# LED_Cube_5x5x5.net
KiCad netlist of a schematic drawn in EAGLE
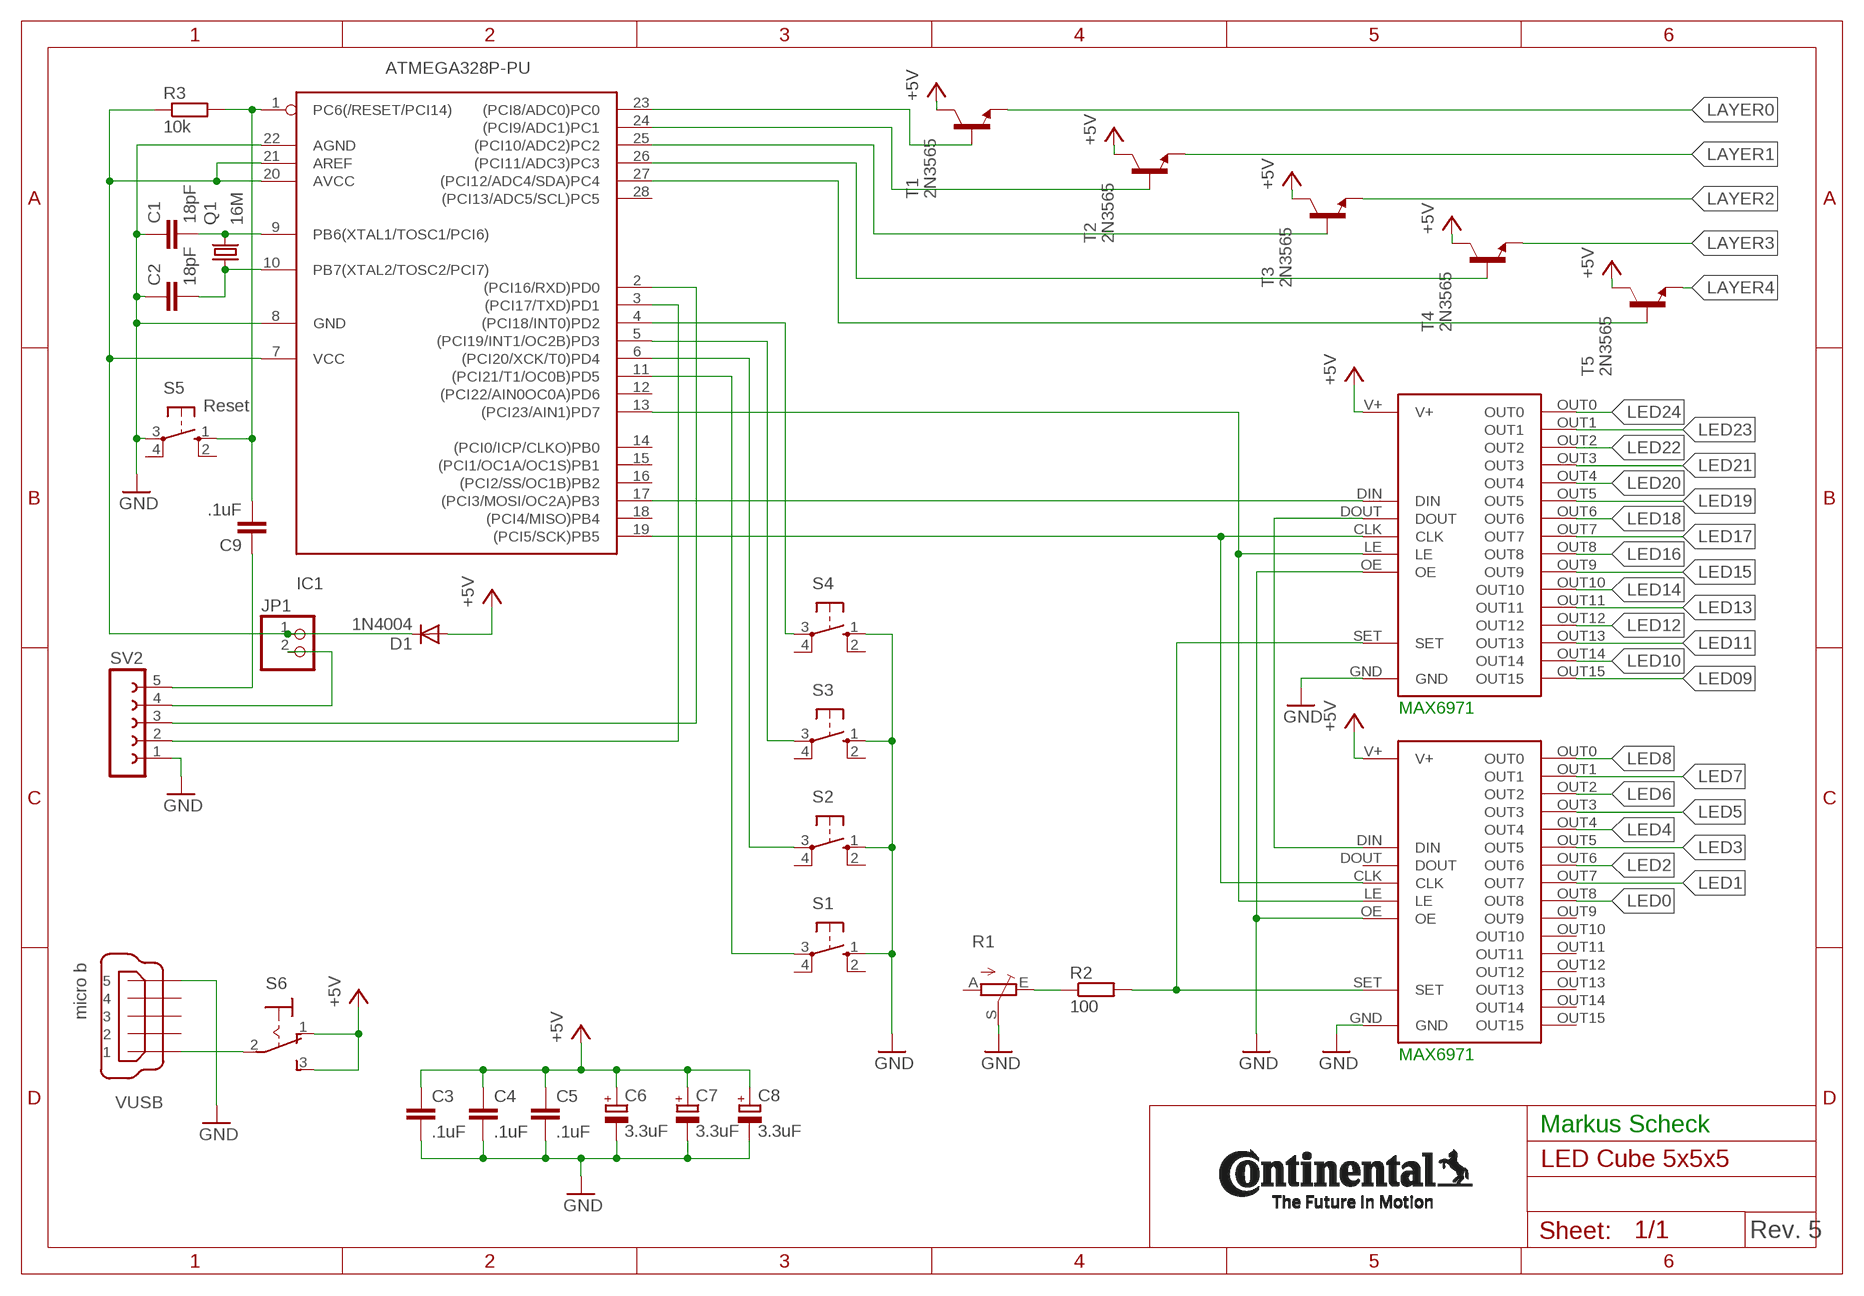
[diagram p0: schematic, sheet 1]

(export (version "E")
  (design (tool "Eeschema 10.0.6"))
  (components
    (comp (ref "C1")
      (value "18pF")
      (footprint "eagle-import:C2.5-3")
      (libsource (lib "eagle-import") (part "C2,5-3"))
    )
    (comp (ref "C2")
      (value "18pF")
      (footprint "eagle-import:C2.5-3")
      (libsource (lib "eagle-import") (part "C2,5-3"))
    )
    (comp (ref "C3")
      (value ".1uF")
      (footprint "eagle-import:C2.5-3")
      (libsource (lib "eagle-import") (part "C2,5-3"))
    )
    (comp (ref "C4")
      (value ".1uF")
      (footprint "eagle-import:C2.5-3")
      (libsource (lib "eagle-import") (part "C2,5-3"))
    )
    (comp (ref "C5")
      (value ".1uF")
      (footprint "eagle-import:C2.5-3")
      (libsource (lib "eagle-import") (part "C2,5-3"))
    )
    (comp (ref "C6")
      (value "3.3uF")
      (footprint "eagle-import:B45181A")
      (libsource (lib "eagle-import") (part "CPOL-EUB45181A"))
    )
    (comp (ref "C7")
      (value "3.3uF")
      (footprint "eagle-import:B45181A")
      (libsource (lib "eagle-import") (part "CPOL-EUB45181A"))
    )
    (comp (ref "C8")
      (value "3.3uF")
      (footprint "eagle-import:B45181A")
      (libsource (lib "eagle-import") (part "CPOL-EUB45181A"))
    )
    (comp (ref "C9")
      (value ".1uF")
      (footprint "eagle-import:C2.5-2")
      (libsource (lib "eagle-import") (part "C2.5/2"))
    )
    (comp (ref "D1")
      (value "1N4004")
      (footprint "eagle-import:DO41-10")
      (libsource (lib "eagle-import") (part "1N4004"))
    )
    (comp (ref "IC1")
      (value "ATMEGA328P-PU")
      (footprint "eagle-import:DIL28-3")
      (libsource (lib "eagle-import") (part "ATMEGA328PV-10"))
    )
    (comp (ref "JP1")
      (value "PINHD-1X2")
      (footprint "eagle-import:1X02")
      (libsource (lib "eagle-import") (part "PINHD-1X2"))
    )
    (comp (ref "Q1")
      (value "16M")
      (footprint "eagle-import:11.4X4.5")
      (libsource (lib "eagle-import") (part "KX-KS"))
    )
    (comp (ref "R1")
      (value "TRIM_EU-CA6V")
      (footprint "eagle-import:CA6V")
      (libsource (lib "eagle-import") (part "TRIM_EU-CA6V"))
    )
    (comp (ref "R2")
      (value "100")
      (footprint "eagle-import:0204_7")
      (libsource (lib "eagle-import") (part "R-EU_0204/7"))
    )
    (comp (ref "R3")
      (value "10k")
      (footprint "eagle-import:0204_7")
      (libsource (lib "eagle-import") (part "R0204/7"))
    )
    (comp (ref "S1")
      (value "10-XX")
      (footprint "eagle-import:B3F-10XX")
      (fields (field (name "MPN") "B3F-1000"))
      (libsource (lib "eagle-import") (part "10-XX"))
    )
    (comp (ref "S2")
      (value "10-XX")
      (footprint "eagle-import:B3F-10XX")
      (fields (field (name "MPN") "B3F-1000"))
      (libsource (lib "eagle-import") (part "10-XX"))
    )
    (comp (ref "S3")
      (value "10-XX")
      (footprint "eagle-import:B3F-10XX")
      (fields (field (name "MPN") "B3F-1000"))
      (libsource (lib "eagle-import") (part "10-XX"))
    )
    (comp (ref "S4")
      (value "10-XX")
      (footprint "eagle-import:B3F-10XX")
      (fields (field (name "MPN") "B3F-1000"))
      (libsource (lib "eagle-import") (part "10-XX"))
    )
    (comp (ref "S5")
      (value "Reset")
      (footprint "eagle-import:B3F-10XX")
      (fields (field (name "MPN") "B3F-1000"))
      (libsource (lib "eagle-import") (part "10-XX"))
    )
    (comp (ref "S6")
      (value "320-916")
      (footprint "eagle-import:320-916")
      (libsource (lib "eagle-import") (part "320-916"))
    )
    (comp (ref "SV2")
      (value "FE05-1")
      (footprint "eagle-import:FE05-1")
      (libsource (lib "eagle-import") (part "FE05-1"))
    )
    (comp (ref "T1")
      (value "2N3565")
      (footprint "eagle-import:TO92")
      (libsource (lib "eagle-import") (part "2N3565"))
    )
    (comp (ref "T2")
      (value "2N3565")
      (footprint "eagle-import:TO92")
      (libsource (lib "eagle-import") (part "2N3565"))
    )
    (comp (ref "T3")
      (value "2N3565")
      (footprint "eagle-import:TO92")
      (libsource (lib "eagle-import") (part "2N3565"))
    )
    (comp (ref "T4")
      (value "2N3565")
      (footprint "eagle-import:TO92")
      (libsource (lib "eagle-import") (part "2N3565"))
    )
    (comp (ref "T5")
      (value "2N3565")
      (footprint "eagle-import:TO92")
      (libsource (lib "eagle-import") (part "2N3565"))
    )
    (comp (ref "U$1")
      (value "MAX6971")
      (footprint "eagle-import:MAX6971")
      (libsource (lib "eagle-import") (part "MAX6971"))
    )
    (comp (ref "U$2")
      (value "MAX6971")
      (footprint "eagle-import:MAX6971")
      (libsource (lib "eagle-import") (part "MAX6971"))
    )
    (comp (ref "VUSB")
      (value "micro b")
      (footprint "eagle-import:32005-201")
      (libsource (lib "eagle-import") (part "MINI-USB-32005-201"))
    )
  )
  (nets
    (net (code "1") (name "+5V") (class "Default")
      (node (ref "C3") (pin "1") (pinfunction "1_1") (pintype "passive"))
      (node (ref "C4") (pin "1") (pinfunction "1_1") (pintype "passive"))
      (node (ref "C5") (pin "1") (pinfunction "1_1") (pintype "passive"))
      (node (ref "C6") (pin "+") (pinfunction "+_+") (pintype "passive"))
      (node (ref "C7") (pin "+") (pinfunction "+_+") (pintype "passive"))
      (node (ref "C8") (pin "+") (pinfunction "+_+") (pintype "passive"))
      (node (ref "D1") (pin "A") (pinfunction "A_A") (pintype "passive"))
      (node (ref "S6") (pin "1") (pinfunction "O_1") (pintype "passive"))
      (node (ref "S6") (pin "3") (pinfunction "S_3") (pintype "passive"))
      (node (ref "T1") (pin "1") (pinfunction "C_1") (pintype "passive"))
      (node (ref "T2") (pin "1") (pinfunction "C_1") (pintype "passive"))
      (node (ref "T3") (pin "1") (pinfunction "C_1") (pintype "passive"))
      (node (ref "T4") (pin "1") (pinfunction "C_1") (pintype "passive"))
      (node (ref "T5") (pin "1") (pinfunction "C_1") (pintype "passive"))
      (node (ref "U$1") (pin "V+") (pinfunction "V+_V+") (pintype "bidirectional"))
      (node (ref "U$2") (pin "V+") (pinfunction "V+_V+") (pintype "bidirectional"))
    )
    (net (code "2") (name "GND") (class "Default")
      (node (ref "C1") (pin "1") (pinfunction "1_1") (pintype "passive"))
      (node (ref "C2") (pin "1") (pinfunction "1_1") (pintype "passive"))
      (node (ref "C3") (pin "2") (pinfunction "2_2") (pintype "passive"))
      (node (ref "C4") (pin "2") (pinfunction "2_2") (pintype "passive"))
      (node (ref "C5") (pin "2") (pinfunction "2_2") (pintype "passive"))
      (node (ref "C6") (pin "-") (pinfunction "-_-") (pintype "passive"))
      (node (ref "C7") (pin "-") (pinfunction "-_-") (pintype "passive"))
      (node (ref "C8") (pin "-") (pinfunction "-_-") (pintype "passive"))
      (node (ref "IC1") (pin "22") (pinfunction "AGND_22") (pintype "bidirectional"))
      (node (ref "IC1") (pin "8") (pinfunction "GND_8") (pintype "bidirectional"))
      (node (ref "R1") (pin "S") (pinfunction "S_S") (pintype "passive"))
      (node (ref "S1") (pin "1") (pinfunction "S_1") (pintype "passive"))
      (node (ref "S2") (pin "1") (pinfunction "S_1") (pintype "passive"))
      (node (ref "S3") (pin "1") (pinfunction "S_1") (pintype "passive"))
      (node (ref "S4") (pin "1") (pinfunction "S_1") (pintype "passive"))
      (node (ref "S5") (pin "3") (pinfunction "P_3") (pintype "passive"))
      (node (ref "SV2") (pin "1") (pinfunction "1_1") (pintype "passive"))
      (node (ref "U$1") (pin "GND") (pinfunction "GND_GND") (pintype "bidirectional"))
      (node (ref "U$1") (pin "OE") (pinfunction "OE_OE") (pintype "bidirectional"))
      (node (ref "U$2") (pin "GND") (pinfunction "GND_GND") (pintype "bidirectional"))
      (node (ref "U$2") (pin "OE") (pinfunction "OE_OE") (pintype "bidirectional"))
      (node (ref "VUSB") (pin "5") (pinfunction "5_5") (pintype "passive"))
    )
    (net (code "3") (name "LAYER0") (class "Default")
      (node (ref "T1") (pin "3") (pinfunction "E_3") (pintype "passive"))
    )
    (net (code "4") (name "LAYER1") (class "Default")
      (node (ref "T2") (pin "3") (pinfunction "E_3") (pintype "passive"))
    )
    (net (code "5") (name "LAYER2") (class "Default")
      (node (ref "T3") (pin "3") (pinfunction "E_3") (pintype "passive"))
    )
    (net (code "6") (name "LAYER3") (class "Default")
      (node (ref "T4") (pin "3") (pinfunction "E_3") (pintype "passive"))
    )
    (net (code "7") (name "LAYER4") (class "Default")
      (node (ref "T5") (pin "3") (pinfunction "E_3") (pintype "passive"))
    )
    (net (code "8") (name "LED0") (class "Default")
      (node (ref "U$1") (pin "OUT8") (pinfunction "OUT8_OUT8") (pintype "bidirectional"))
    )
    (net (code "9") (name "LED1") (class "Default")
      (node (ref "U$1") (pin "OUT7") (pinfunction "OUT7_OUT7") (pintype "bidirectional"))
    )
    (net (code "10") (name "LED2") (class "Default")
      (node (ref "U$1") (pin "OUT6") (pinfunction "OUT6_OUT6") (pintype "bidirectional"))
    )
    (net (code "11") (name "LED3") (class "Default")
      (node (ref "U$1") (pin "OUT5") (pinfunction "OUT5_OUT5") (pintype "bidirectional"))
    )
    (net (code "12") (name "LED4") (class "Default")
      (node (ref "U$1") (pin "OUT4") (pinfunction "OUT4_OUT4") (pintype "bidirectional"))
    )
    (net (code "13") (name "LED5") (class "Default")
      (node (ref "U$1") (pin "OUT3") (pinfunction "OUT3_OUT3") (pintype "bidirectional"))
    )
    (net (code "14") (name "LED6") (class "Default")
      (node (ref "U$1") (pin "OUT2") (pinfunction "OUT2_OUT2") (pintype "bidirectional"))
    )
    (net (code "15") (name "LED7") (class "Default")
      (node (ref "U$1") (pin "OUT1") (pinfunction "OUT1_OUT1") (pintype "bidirectional"))
    )
    (net (code "16") (name "LED8") (class "Default")
      (node (ref "U$1") (pin "OUT0") (pinfunction "OUT0_OUT0") (pintype "bidirectional"))
    )
    (net (code "17") (name "LED09") (class "Default")
      (node (ref "U$2") (pin "OUT15") (pinfunction "OUT15_OUT15") (pintype "bidirectional"))
    )
    (net (code "18") (name "LED10") (class "Default")
      (node (ref "U$2") (pin "OUT14") (pinfunction "OUT14_OUT14") (pintype "bidirectional"))
    )
    (net (code "19") (name "LED11") (class "Default")
      (node (ref "U$2") (pin "OUT13") (pinfunction "OUT13_OUT13") (pintype "bidirectional"))
    )
    (net (code "20") (name "LED12") (class "Default")
      (node (ref "U$2") (pin "OUT12") (pinfunction "OUT12_OUT12") (pintype "bidirectional"))
    )
    (net (code "21") (name "LED13") (class "Default")
      (node (ref "U$2") (pin "OUT11") (pinfunction "OUT11_OUT11") (pintype "bidirectional"))
    )
    (net (code "22") (name "LED14") (class "Default")
      (node (ref "U$2") (pin "OUT10") (pinfunction "OUT10_OUT10") (pintype "bidirectional"))
    )
    (net (code "23") (name "LED15") (class "Default")
      (node (ref "U$2") (pin "OUT9") (pinfunction "OUT9_OUT9") (pintype "bidirectional"))
    )
    (net (code "24") (name "LED16") (class "Default")
      (node (ref "U$2") (pin "OUT8") (pinfunction "OUT8_OUT8") (pintype "bidirectional"))
    )
    (net (code "25") (name "LED17") (class "Default")
      (node (ref "U$2") (pin "OUT7") (pinfunction "OUT7_OUT7") (pintype "bidirectional"))
    )
    (net (code "26") (name "LED18") (class "Default")
      (node (ref "U$2") (pin "OUT6") (pinfunction "OUT6_OUT6") (pintype "bidirectional"))
    )
    (net (code "27") (name "LED19") (class "Default")
      (node (ref "U$2") (pin "OUT5") (pinfunction "OUT5_OUT5") (pintype "bidirectional"))
    )
    (net (code "28") (name "LED20") (class "Default")
      (node (ref "U$2") (pin "OUT4") (pinfunction "OUT4_OUT4") (pintype "bidirectional"))
    )
    (net (code "29") (name "LED21") (class "Default")
      (node (ref "U$2") (pin "OUT3") (pinfunction "OUT3_OUT3") (pintype "bidirectional"))
    )
    (net (code "30") (name "LED22") (class "Default")
      (node (ref "U$2") (pin "OUT2") (pinfunction "OUT2_OUT2") (pintype "bidirectional"))
    )
    (net (code "31") (name "LED23") (class "Default")
      (node (ref "U$2") (pin "OUT1") (pinfunction "OUT1_OUT1") (pintype "bidirectional"))
    )
    (net (code "32") (name "LED24") (class "Default")
      (node (ref "U$2") (pin "OUT0") (pinfunction "OUT0_OUT0") (pintype "bidirectional"))
    )
    (net (code "33") (name "Net-(C9-Pad1)") (class "Default")
      (node (ref "C9") (pin "1") (pinfunction "1_1") (pintype "passive"))
      (node (ref "SV2") (pin "5") (pinfunction "5_5") (pintype "passive"))
    )
    (net (code "34") (name "Net-(IC1-(PCI3{slash}MOSI{slash}OC2A)PB3)") (class "Default")
      (node (ref "IC1") (pin "17") (pinfunction "(PCI3/MOSI/OC2A)PB3_17") (pintype "bidirectional"))
      (node (ref "U$2") (pin "DIN") (pinfunction "DIN_DIN") (pintype "bidirectional"))
    )
    (net (code "35") (name "Net-(IC1-(PCI5{slash}SCK)PB5)") (class "Default")
      (node (ref "IC1") (pin "19") (pinfunction "(PCI5/SCK)PB5_19") (pintype "bidirectional"))
      (node (ref "U$1") (pin "CLK") (pinfunction "CLK_CLK") (pintype "bidirectional"))
      (node (ref "U$2") (pin "CLK") (pinfunction "CLK_CLK") (pintype "bidirectional"))
    )
    (net (code "36") (name "Net-(IC1-(PCI8{slash}ADC0)PC0)") (class "Default")
      (node (ref "IC1") (pin "23") (pinfunction "(PCI8/ADC0)PC0_23") (pintype "bidirectional"))
      (node (ref "T1") (pin "2") (pinfunction "B_2") (pintype "passive"))
    )
    (net (code "37") (name "Net-(IC1-(PCI9{slash}ADC1)PC1)") (class "Default")
      (node (ref "IC1") (pin "24") (pinfunction "(PCI9/ADC1)PC1_24") (pintype "bidirectional"))
      (node (ref "T2") (pin "2") (pinfunction "B_2") (pintype "passive"))
    )
    (net (code "38") (name "Net-(IC1-(PCI10{slash}ADC2)PC2)") (class "Default")
      (node (ref "IC1") (pin "25") (pinfunction "(PCI10/ADC2)PC2_25") (pintype "bidirectional"))
      (node (ref "T3") (pin "2") (pinfunction "B_2") (pintype "passive"))
    )
    (net (code "39") (name "Net-(IC1-(PCI11{slash}ADC3)PC3)") (class "Default")
      (node (ref "IC1") (pin "26") (pinfunction "(PCI11/ADC3)PC3_26") (pintype "bidirectional"))
      (node (ref "T4") (pin "2") (pinfunction "B_2") (pintype "passive"))
    )
    (net (code "40") (name "Net-(IC1-(PCI12{slash}ADC4{slash}SDA)PC4)") (class "Default")
      (node (ref "IC1") (pin "27") (pinfunction "(PCI12/ADC4/SDA)PC4_27") (pintype "bidirectional"))
      (node (ref "T5") (pin "2") (pinfunction "B_2") (pintype "passive"))
    )
    (net (code "41") (name "Net-(IC1-(PCI16{slash}RXD)PD0)") (class "Default")
      (node (ref "IC1") (pin "2") (pinfunction "(PCI16/RXD)PD0_2") (pintype "bidirectional"))
      (node (ref "SV2") (pin "3") (pinfunction "3_3") (pintype "passive"))
    )
    (net (code "42") (name "Net-(IC1-(PCI17{slash}TXD)PD1)") (class "Default")
      (node (ref "IC1") (pin "3") (pinfunction "(PCI17/TXD)PD1_3") (pintype "bidirectional"))
      (node (ref "SV2") (pin "2") (pinfunction "2_2") (pintype "passive"))
    )
    (net (code "43") (name "Net-(IC1-(PCI18{slash}INT0)PD2)") (class "Default")
      (node (ref "IC1") (pin "4") (pinfunction "(PCI18/INT0)PD2_4") (pintype "bidirectional"))
      (node (ref "S4") (pin "3") (pinfunction "P_3") (pintype "passive"))
    )
    (net (code "44") (name "Net-(IC1-(PCI19{slash}INT1{slash}OC2B)PD3)") (class "Default")
      (node (ref "IC1") (pin "5") (pinfunction "(PCI19/INT1/OC2B)PD3_5") (pintype "bidirectional"))
      (node (ref "S3") (pin "3") (pinfunction "P_3") (pintype "passive"))
    )
    (net (code "45") (name "Net-(IC1-(PCI20{slash}XCK{slash}T0)PD4)") (class "Default")
      (node (ref "IC1") (pin "6") (pinfunction "(PCI20/XCK/T0)PD4_6") (pintype "bidirectional"))
      (node (ref "S2") (pin "3") (pinfunction "P_3") (pintype "passive"))
    )
    (net (code "46") (name "Net-(IC1-(PCI21{slash}T1{slash}OC0B)PD5)") (class "Default")
      (node (ref "IC1") (pin "11") (pinfunction "(PCI21/T1/OC0B)PD5_11") (pintype "bidirectional"))
      (node (ref "S1") (pin "3") (pinfunction "P_3") (pintype "passive"))
    )
    (net (code "47") (name "Net-(IC1-(PCI23{slash}AIN1)PD7)") (class "Default")
      (node (ref "IC1") (pin "13") (pinfunction "(PCI23/AIN1)PD7_13") (pintype "bidirectional"))
      (node (ref "U$1") (pin "LE") (pinfunction "LE_LE") (pintype "bidirectional"))
      (node (ref "U$2") (pin "LE") (pinfunction "LE_LE") (pintype "bidirectional"))
    )
    (net (code "48") (name "Net-(IC1-AREF)") (class "Default")
      (node (ref "D1") (pin "C") (pinfunction "C_C") (pintype "passive"))
      (node (ref "IC1") (pin "20") (pinfunction "AVCC_20") (pintype "bidirectional"))
      (node (ref "IC1") (pin "21") (pinfunction "AREF_21") (pintype "bidirectional"))
      (node (ref "IC1") (pin "7") (pinfunction "VCC_7") (pintype "bidirectional"))
      (node (ref "JP1") (pin "1") (pinfunction "1_1") (pintype "passive"))
      (node (ref "R3") (pin "1") (pinfunction "1_1") (pintype "passive"))
    )
    (net (code "49") (name "Net-(IC1-PB6(XTAL1{slash}TOSC1{slash}PCI6))") (class "Default")
      (node (ref "C1") (pin "2") (pinfunction "2_2") (pintype "passive"))
      (node (ref "IC1") (pin "9") (pinfunction "PB6(XTAL1/TOSC1/PCI6)_9") (pintype "bidirectional"))
      (node (ref "Q1") (pin "2") (pinfunction "2_2") (pintype "passive"))
    )
    (net (code "50") (name "Net-(IC1-PB7(XTAL2{slash}TOSC2{slash}PCI7))") (class "Default")
      (node (ref "C2") (pin "2") (pinfunction "2_2") (pintype "passive"))
      (node (ref "IC1") (pin "10") (pinfunction "PB7(XTAL2/TOSC2/PCI7)_10") (pintype "bidirectional"))
      (node (ref "Q1") (pin "1") (pinfunction "1_1") (pintype "passive"))
    )
    (net (code "51") (name "Net-(IC1-PC6({slash}RESET{slash}PCI14))") (class "Default")
      (node (ref "C9") (pin "2") (pinfunction "2_2") (pintype "passive"))
      (node (ref "IC1") (pin "1") (pinfunction "PC6(/RESET/PCI14)_1") (pintype "bidirectional"))
      (node (ref "R3") (pin "2") (pinfunction "2_2") (pintype "passive"))
      (node (ref "S5") (pin "1") (pinfunction "S_1") (pintype "passive"))
    )
    (net (code "52") (name "Net-(JP1-Pad2)") (class "Default")
      (node (ref "JP1") (pin "2") (pinfunction "2_2") (pintype "passive"))
      (node (ref "SV2") (pin "4") (pinfunction "4_4") (pintype "passive"))
    )
    (net (code "53") (name "Net-(R1-PadE)") (class "Default")
      (node (ref "R1") (pin "E") (pinfunction "E_E") (pintype "passive"))
      (node (ref "R2") (pin "1") (pinfunction "1_1") (pintype "passive"))
    )
    (net (code "54") (name "Net-(R2-Pad2)") (class "Default")
      (node (ref "R2") (pin "2") (pinfunction "2_2") (pintype "passive"))
      (node (ref "U$1") (pin "SET") (pinfunction "SET_SET") (pintype "bidirectional"))
      (node (ref "U$2") (pin "SET") (pinfunction "SET_SET") (pintype "bidirectional"))
    )
    (net (code "55") (name "Net-(S6-P)") (class "Default")
      (node (ref "S6") (pin "2") (pinfunction "P_2") (pintype "passive"))
      (node (ref "VUSB") (pin "1") (pinfunction "1_1") (pintype "passive"))
    )
    (net (code "56") (name "Net-(U$1-PadDIN)") (class "Default")
      (node (ref "U$1") (pin "DIN") (pinfunction "DIN_DIN") (pintype "bidirectional"))
      (node (ref "U$2") (pin "DOUT") (pinfunction "DOUT_DOUT") (pintype "bidirectional"))
    )
    (net (code "57") (name "unconnected-(IC1-(PCI0{slash}ICP{slash}CLKO)PB0-Pad14)") (class "Default")
      (node (ref "IC1") (pin "14") (pinfunction "(PCI0/ICP/CLKO)PB0_14") (pintype "bidirectional"))
    )
    (net (code "58") (name "unconnected-(IC1-(PCI1{slash}OC1A{slash}OC1S)PB1-Pad15)") (class "Default")
      (node (ref "IC1") (pin "15") (pinfunction "(PCI1/OC1A/OC1S)PB1_15") (pintype "bidirectional"))
    )
    (net (code "59") (name "unconnected-(IC1-(PCI2{slash}SS{slash}OC1B)PB2-Pad16)") (class "Default")
      (node (ref "IC1") (pin "16") (pinfunction "(PCI2/SS/OC1B)PB2_16") (pintype "bidirectional"))
    )
    (net (code "60") (name "unconnected-(IC1-(PCI4{slash}MISO)PB4-Pad18)") (class "Default")
      (node (ref "IC1") (pin "18") (pinfunction "(PCI4/MISO)PB4_18") (pintype "bidirectional"))
    )
    (net (code "61") (name "unconnected-(IC1-(PCI13{slash}ADC5{slash}SCL)PC5-Pad28)") (class "Default")
      (node (ref "IC1") (pin "28") (pinfunction "(PCI13/ADC5/SCL)PC5_28") (pintype "bidirectional"))
    )
    (net (code "62") (name "unconnected-(IC1-(PCI22{slash}AIN0OC0A)PD6-Pad12)") (class "Default")
      (node (ref "IC1") (pin "12") (pinfunction "(PCI22/AIN0OC0A)PD6_12") (pintype "bidirectional"))
    )
    (net (code "63") (name "unconnected-(R1-PadA)") (class "Default")
      (node (ref "R1") (pin "A") (pinfunction "A_A") (pintype "passive"))
    )
    (net (code "64") (name "unconnected-(S1-P1-Pad4)") (class "Default")
      (node (ref "S1") (pin "4") (pinfunction "P1_4") (pintype "passive"))
    )
    (net (code "65") (name "unconnected-(S1-S1-Pad2)") (class "Default")
      (node (ref "S1") (pin "2") (pinfunction "S1_2") (pintype "passive"))
    )
    (net (code "66") (name "unconnected-(S2-P1-Pad4)") (class "Default")
      (node (ref "S2") (pin "4") (pinfunction "P1_4") (pintype "passive"))
    )
    (net (code "67") (name "unconnected-(S2-S1-Pad2)") (class "Default")
      (node (ref "S2") (pin "2") (pinfunction "S1_2") (pintype "passive"))
    )
    (net (code "68") (name "unconnected-(S3-P1-Pad4)") (class "Default")
      (node (ref "S3") (pin "4") (pinfunction "P1_4") (pintype "passive"))
    )
    (net (code "69") (name "unconnected-(S3-S1-Pad2)") (class "Default")
      (node (ref "S3") (pin "2") (pinfunction "S1_2") (pintype "passive"))
    )
    (net (code "70") (name "unconnected-(S4-P1-Pad4)") (class "Default")
      (node (ref "S4") (pin "4") (pinfunction "P1_4") (pintype "passive"))
    )
    (net (code "71") (name "unconnected-(S4-S1-Pad2)") (class "Default")
      (node (ref "S4") (pin "2") (pinfunction "S1_2") (pintype "passive"))
    )
    (net (code "72") (name "unconnected-(S5-P1-Pad4)") (class "Default")
      (node (ref "S5") (pin "4") (pinfunction "P1_4") (pintype "passive"))
    )
    (net (code "73") (name "unconnected-(S5-S1-Pad2)") (class "Default")
      (node (ref "S5") (pin "2") (pinfunction "S1_2") (pintype "passive"))
    )
    (net (code "74") (name "unconnected-(U$1-PadDOUT)") (class "Default")
      (node (ref "U$1") (pin "DOUT") (pinfunction "DOUT_DOUT") (pintype "bidirectional"))
    )
    (net (code "75") (name "unconnected-(U$1-PadOUT9)") (class "Default")
      (node (ref "U$1") (pin "OUT9") (pinfunction "OUT9_OUT9") (pintype "bidirectional"))
    )
    (net (code "76") (name "unconnected-(U$1-PadOUT10)") (class "Default")
      (node (ref "U$1") (pin "OUT10") (pinfunction "OUT10_OUT10") (pintype "bidirectional"))
    )
    (net (code "77") (name "unconnected-(U$1-PadOUT11)") (class "Default")
      (node (ref "U$1") (pin "OUT11") (pinfunction "OUT11_OUT11") (pintype "bidirectional"))
    )
    (net (code "78") (name "unconnected-(U$1-PadOUT12)") (class "Default")
      (node (ref "U$1") (pin "OUT12") (pinfunction "OUT12_OUT12") (pintype "bidirectional"))
    )
    (net (code "79") (name "unconnected-(U$1-PadOUT13)") (class "Default")
      (node (ref "U$1") (pin "OUT13") (pinfunction "OUT13_OUT13") (pintype "bidirectional"))
    )
    (net (code "80") (name "unconnected-(U$1-PadOUT14)") (class "Default")
      (node (ref "U$1") (pin "OUT14") (pinfunction "OUT14_OUT14") (pintype "bidirectional"))
    )
    (net (code "81") (name "unconnected-(U$1-PadOUT15)") (class "Default")
      (node (ref "U$1") (pin "OUT15") (pinfunction "OUT15_OUT15") (pintype "bidirectional"))
    )
    (net (code "82") (name "unconnected-(VUSB-Pad2)") (class "Default")
      (node (ref "VUSB") (pin "2") (pinfunction "2_2") (pintype "passive"))
    )
    (net (code "83") (name "unconnected-(VUSB-Pad3)") (class "Default")
      (node (ref "VUSB") (pin "3") (pinfunction "3_3") (pintype "passive"))
    )
    (net (code "84") (name "unconnected-(VUSB-Pad4)") (class "Default")
      (node (ref "VUSB") (pin "4") (pinfunction "4_4") (pintype "passive"))
    )
  )
)
